# ac-motor-controller-mk-1_0.net
KiCad netlist of a schematic drawn in EAGLE
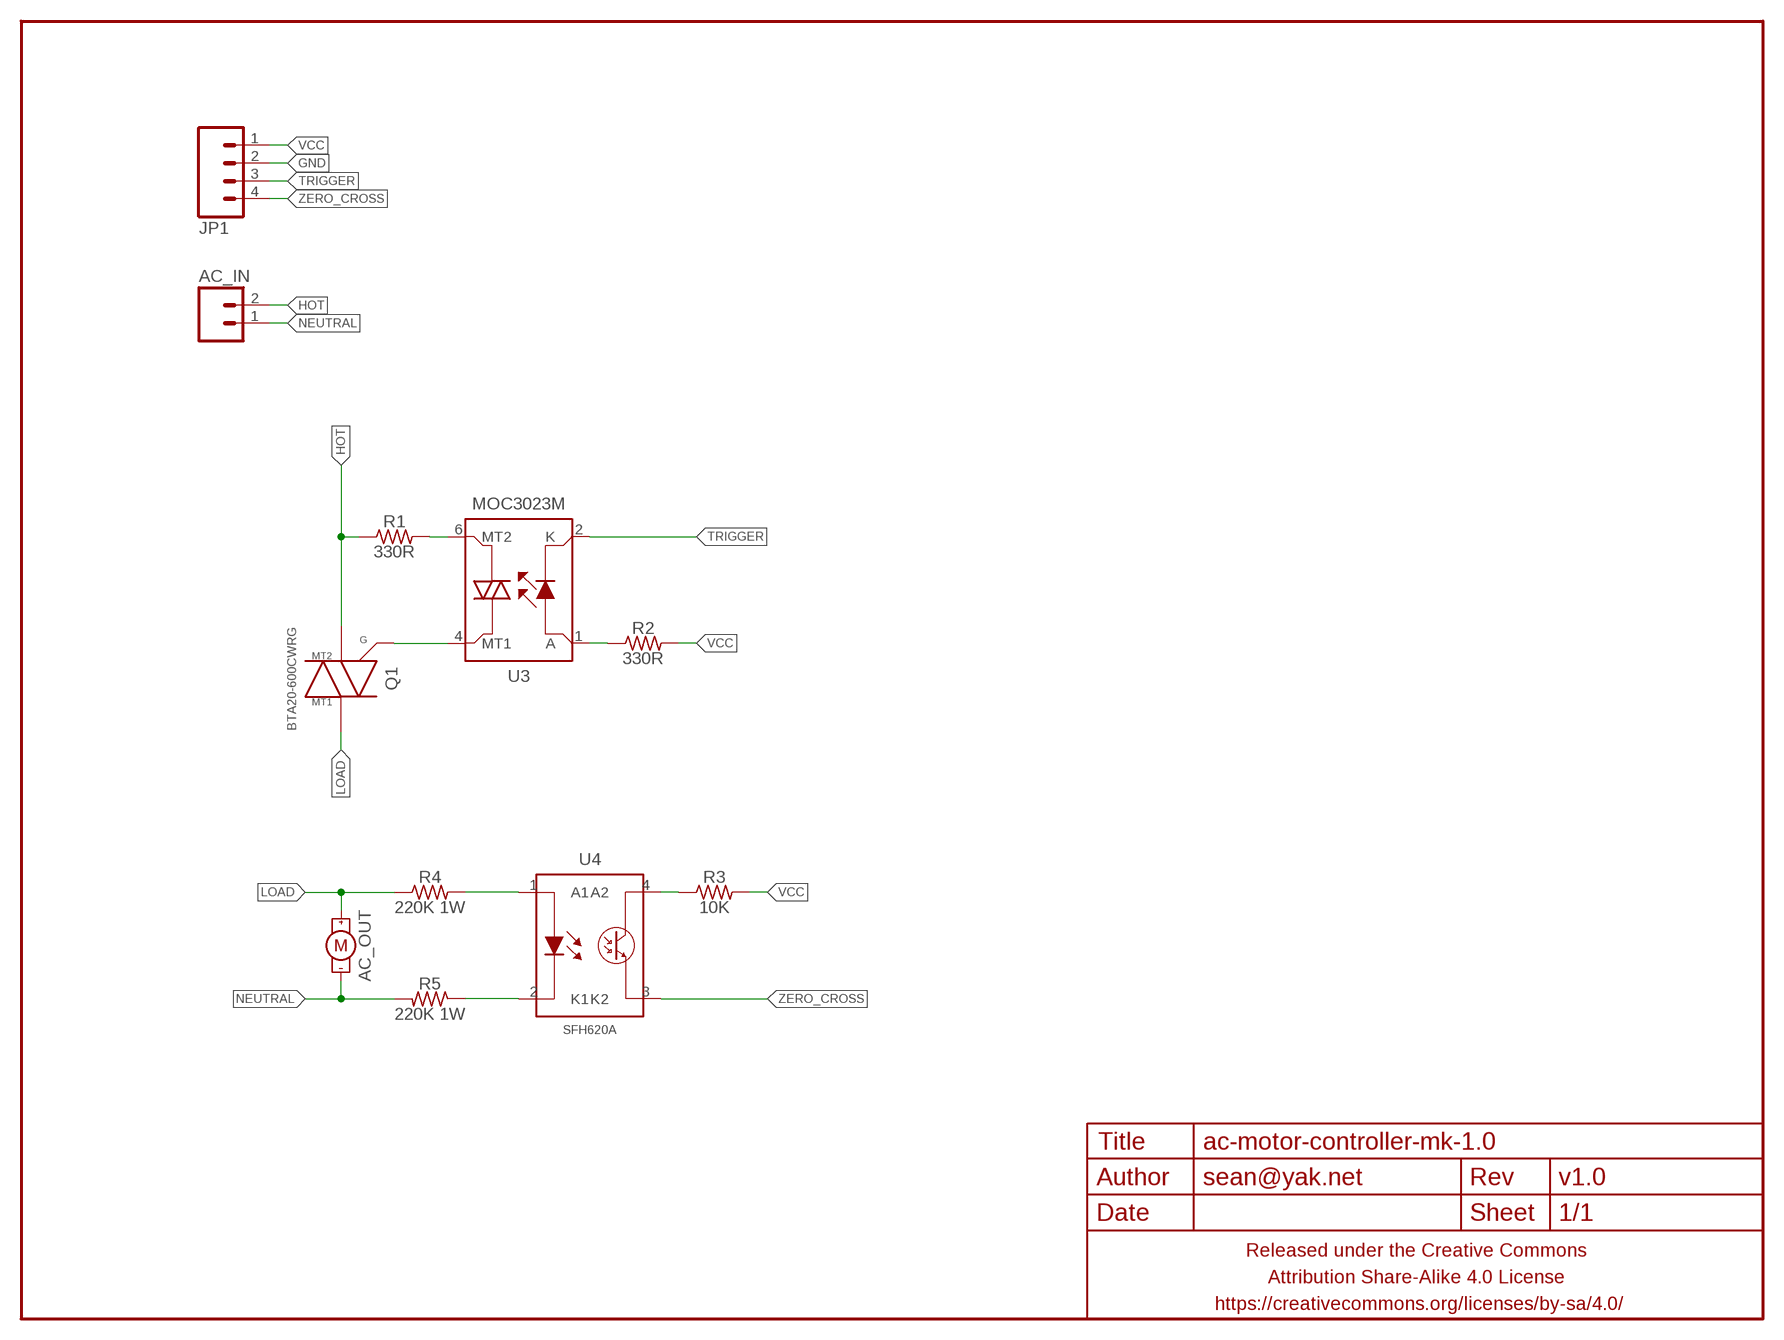
[diagram p0: schematic, sheet 1]

(export (version "E")
  (design (tool "Eeschema 10.0.6"))
  (components
    (comp (ref "AC_IN")
      (value "SCREWTERMINAL-25MM")
      (footprint "eagle-import:SCREWTERM-5MM-2")
      (libsource (lib "eagle-import") (part "SCREWTERMINAL-25MM"))
    )
    (comp (ref "AC_OUT")
      (value "MOTOR5MM-SCREW-TERM")
      (footprint "eagle-import:1X02_5MM_SCREW")
      (libsource (lib "eagle-import") (part "MOTOR5MM-SCREW-TERM"))
    )
    (comp (ref "FRAME1")
      (value "FRAME-LETTERNO_PACKAGE")
      (footprint "eagle-import:DUMMY")
      (fields (field (name "DESIGNER") "sean@yak.net") (field (name "VERSION") "v1.0"))
      (libsource (lib "eagle-import") (part "FRAME-LETTERNO_PACKAGE"))
    )
    (comp (ref "JP1")
      (value "M04JST-PTH-CENTERED")
      (footprint "eagle-import:JST-4-PH-VERT-PTH-CENTERED")
      (libsource (lib "eagle-import") (part "M04JST-PTH-CENTERED"))
    )
    (comp (ref "Q1")
      (value "BTA20-600CWRG")
      (footprint "eagle-import:TO220V")
      (libsource (lib "eagle-import") (part "TRIACTO-220-VERT"))
    )
    (comp (ref "R1")
      (value "330R")
      (footprint "eagle-import:RESISTOR-AXIAL-PTH-5.08MM")
      (libsource (lib "eagle-import") (part "RESISTORPTH-AXIAL-5.08MM"))
    )
    (comp (ref "R2")
      (value "330R")
      (footprint "eagle-import:RESISTOR-AXIAL-PTH-5.08MM")
      (libsource (lib "eagle-import") (part "RESISTORPTH-AXIAL-5.08MM"))
    )
    (comp (ref "R3")
      (value "10K")
      (footprint "eagle-import:RESISTOR-AXIAL-PTH-5.08MM")
      (libsource (lib "eagle-import") (part "RESISTORPTH-AXIAL-5.08MM"))
    )
    (comp (ref "R4")
      (value "220K 1W")
      (footprint "eagle-import:RESISTOR-AXIAL-PTH-10.16MM")
      (libsource (lib "eagle-import") (part "RESISTORPTH-AXIAL-10.16MM"))
    )
    (comp (ref "R5")
      (value "220K 1W")
      (footprint "eagle-import:RESISTOR-AXIAL-PTH-10.16MM")
      (libsource (lib "eagle-import") (part "RESISTORPTH-AXIAL-10.16MM"))
    )
    (comp (ref "U3")
      (value "MOC3023M")
      (footprint "eagle-import:DIP06")
      (libsource (lib "eagle-import") (part "MOC30XXMOC30XXM-DIP6"))
    )
    (comp (ref "U4")
      (value "SFH620A")
      (footprint "eagle-import:DIL04")
      (libsource (lib "eagle-import") (part "OPTOISOLATORDIP4"))
    )
  )
  (nets
    (net (code "1") (name "GND") (class "Default")
      (node (ref "JP1") (pin "2") (pinfunction "2_2") (pintype "passive"))
    )
    (net (code "2") (name "HOT") (class "Default")
      (node (ref "AC_IN") (pin "2") (pinfunction "2_2") (pintype "passive"))
      (node (ref "Q1") (pin "2") (pinfunction "MT2_2") (pintype "bidirectional"))
      (node (ref "R1") (pin "P$1") (pinfunction "1_P$1") (pintype "passive"))
    )
    (net (code "3") (name "LOAD") (class "Default")
      (node (ref "AC_OUT") (pin "1") (pinfunction "+_1") (pintype "bidirectional"))
      (node (ref "Q1") (pin "1") (pinfunction "MT1_1") (pintype "bidirectional"))
      (node (ref "R4") (pin "P$1") (pinfunction "1_P$1") (pintype "passive"))
    )
    (net (code "4") (name "NEUTRAL") (class "Default")
      (node (ref "AC_IN") (pin "1") (pinfunction "1_1") (pintype "passive"))
      (node (ref "AC_OUT") (pin "2") (pinfunction "-_2") (pintype "bidirectional"))
      (node (ref "R5") (pin "P$2") (pinfunction "2_P$2") (pintype "passive"))
    )
    (net (code "5") (name "Net-(Q1-GATE)") (class "Default")
      (node (ref "Q1") (pin "3") (pinfunction "GATE_3") (pintype "bidirectional"))
      (node (ref "U3") (pin "4") (pinfunction "MT1_4") (pintype "bidirectional"))
    )
    (net (code "6") (name "Net-(R1-2)") (class "Default")
      (node (ref "R1") (pin "P$2") (pinfunction "2_P$2") (pintype "passive"))
      (node (ref "U3") (pin "6") (pinfunction "MT2_6") (pintype "bidirectional"))
    )
    (net (code "7") (name "Net-(R2-1)") (class "Default")
      (node (ref "R2") (pin "P$1") (pinfunction "1_P$1") (pintype "passive"))
      (node (ref "U3") (pin "1") (pinfunction "A_1") (pintype "bidirectional"))
    )
    (net (code "8") (name "Net-(R3-1)") (class "Default")
      (node (ref "R3") (pin "P$1") (pinfunction "1_P$1") (pintype "passive"))
      (node (ref "U4") (pin "4") (pinfunction "A2_4") (pintype "bidirectional"))
    )
    (net (code "9") (name "Net-(R4-2)") (class "Default")
      (node (ref "R4") (pin "P$2") (pinfunction "2_P$2") (pintype "passive"))
      (node (ref "U4") (pin "1") (pinfunction "A1_1") (pintype "bidirectional"))
    )
    (net (code "10") (name "Net-(R5-1)") (class "Default")
      (node (ref "R5") (pin "P$1") (pinfunction "1_P$1") (pintype "passive"))
      (node (ref "U4") (pin "2") (pinfunction "K1_2") (pintype "bidirectional"))
    )
    (net (code "11") (name "TRIGGER") (class "Default")
      (node (ref "JP1") (pin "3") (pinfunction "3_3") (pintype "passive"))
      (node (ref "U3") (pin "2") (pinfunction "K_2") (pintype "bidirectional"))
    )
    (net (code "12") (name "VCC") (class "Default")
      (node (ref "JP1") (pin "1") (pinfunction "1_1") (pintype "passive"))
      (node (ref "R2") (pin "P$2") (pinfunction "2_P$2") (pintype "passive"))
      (node (ref "R3") (pin "P$2") (pinfunction "2_P$2") (pintype "passive"))
    )
    (net (code "13") (name "ZERO_CROSS") (class "Default")
      (node (ref "JP1") (pin "4") (pinfunction "4_4") (pintype "passive"))
      (node (ref "U4") (pin "3") (pinfunction "K2_3") (pintype "bidirectional"))
    )
  )
)
